# STLink_V3E_Module.net
KiCad netlist of a schematic drawn in Altium Designer
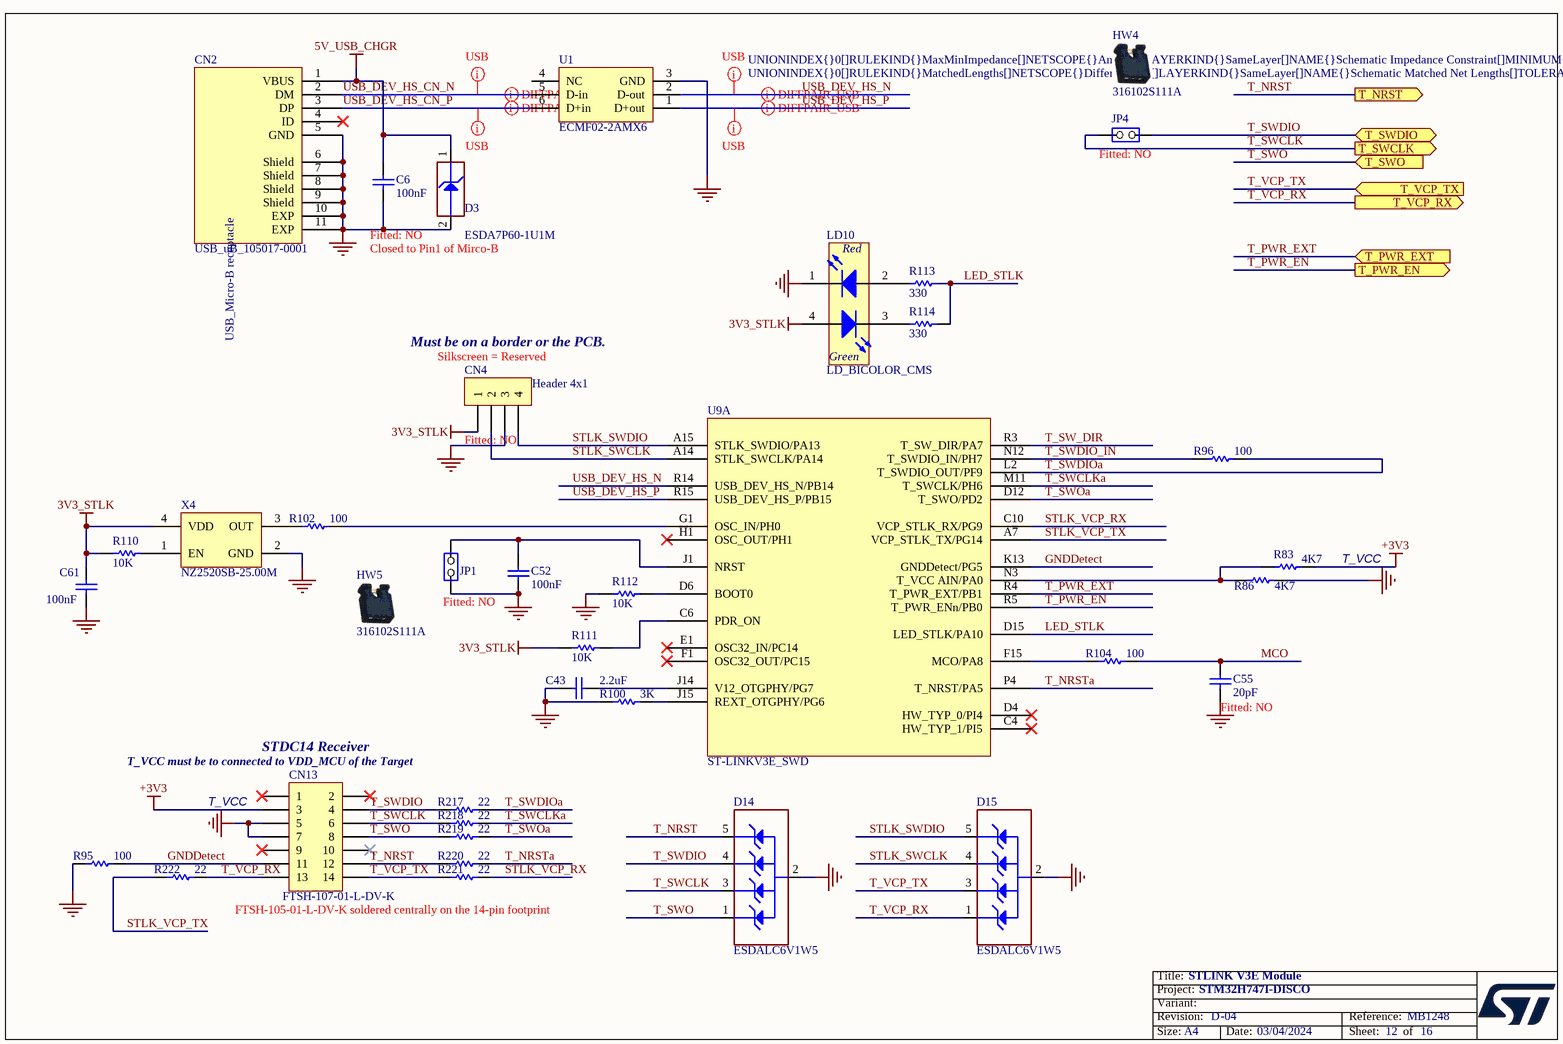
[diagram p0: STLink_V3E_Module.SchDoc]

(export (version "E")
  (design (tool "Eeschema 10.0.6"))
  (components
    (comp (ref "C6")
      (value "100nF")
      (footprint "0402C")
      (description "Capacitor,20pF,50V,NPO,5%,0402")
      (fields
        (field (name "INTERNAL_PART_NUMBER") "MCD-00016")
        (field (name "MANUFACTURER_PART_NUMBER") "CC0402JRNPO9BN200")
        (field (name "FITTED") "NO")
        (field (name "PROVIDED_BY") "Subcon")
      )
      (libsource (lib "MCD_PARTS_database") (part "Capacitor"))
    )
    (comp (ref "C43")
      (value "2.2uF")
      (footprint "0603C")
      (description "Capacitor,2.2uF,10V, X5R,10%,0603")
      (fields
        (field (name "INTERNAL_PART_NUMBER") "MCD-00012")
        (field (name "MANUFACTURER_PART_NUMBER") "CC0603KRX5R6BB225")
        (field (name "PROVIDED_BY") "Subcon")
      )
      (libsource (lib "MCD_PARTS_database") (part "Capacitor"))
    )
    (comp (ref "C52")
      (value "100nF")
      (footprint "0402C")
      (description "Capacitor,100nF,16V,X7R,10%,0402")
      (fields
        (field (name "INTERNAL_PART_NUMBER") "MCD-00102")
        (field (name "MANUFACTURER_PART_NUMBER") "CC0402KRX7R7BB104")
        (field (name "PROVIDED_BY") "Subcon")
      )
      (libsource (lib "MCD_PARTS_database") (part "Capacitor"))
    )
    (comp (ref "C55")
      (value "20pF")
      (footprint "0402C")
      (description "Capacitor,20pF,50V,NPO,5%,0402")
      (fields
        (field (name "INTERNAL_PART_NUMBER") "MCD-00016")
        (field (name "MANUFACTURER_PART_NUMBER") "CC0402JRNPO9BN200")
        (field (name "FITTED") "NO")
        (field (name "PROVIDED_BY") "Subcon")
      )
      (libsource (lib "MCD_PARTS_database") (part "Capacitor"))
    )
    (comp (ref "C61")
      (value "100nF")
      (footprint "0402C")
      (description "Capacitor,100nF,16V,X7R,10%,0402")
      (fields
        (field (name "INTERNAL_PART_NUMBER") "MCD-00102")
        (field (name "MANUFACTURER_PART_NUMBER") "CC0402KRX7R7BB104")
        (field (name "PROVIDED_BY") "Subcon")
      )
      (libsource (lib "MCD_PARTS_database") (part "Capacitor"))
    )
    (comp (ref "CN2")
      (value "USB_uB_105017-0001")
      (footprint "MICRO_USB_B_105017")
      (description "USB-MICRO-B, 0.65mm, RA, SMT, Bottom Mount,")
      (fields
        (field (name "INTERNAL_PART_NUMBER") "MCD-00028")
        (field (name "MANUFACTURER_PART_NUMBER") "1050170001")
        (field (name "PROVIDED_BY") "Subcon")
      )
      (libsource (lib "MCD_PARTS_database") (part "USB_uB_105017.0001"))
    )
    (comp (ref "CN4")
      (value "Header 4x1")
      (footprint "HDR_1X4_2R54")
      (description "Header, 4x1, 2,54mm, VR, TH, Height 5.84mm/2.54mm")
      (fields
        (field (name "INTERNAL_PART_NUMBER") "MCD-00029")
        (field (name "MANUFACTURER_PART_NUMBER") "TSW-104-07-G-S")
        (field (name "FITTED") "NO")
        (field (name "PROVIDED_BY") "Subcon")
      )
      (libsource (lib "MCD_PARTS_database") (part "Header 4x1"))
    )
    (comp (ref "CN13")
      (value "FTSH-107-01-L-DV-K")
      (footprint "FTSH-107-01-L-DV_B")
      (description "Header 7x2, 1.27mm, Dual row, Straight")
      (fields
        (field (name "INTERNAL_PART_NUMBER") "MCD-00592")
        (field (name "MANUFACTURER_PART_NUMBER") "FTSH-107-01-L-DV-009-ES-A")
        (field (name "PROVIDED_BY") "Subcon")
      )
      (libsource (lib "MCD_PARTS_database") (part "Header 7x2"))
    )
    (comp (ref "D3")
      (value "ESDA7P60-1U1M")
      (footprint "DO_2SM_1R6X1_21")
      (description "Dual Transil array for ESD protection")
      (libsource (lib "MCD_TEMP_PCH") (part "ESDALC6V1-1U2"))
    )
    (comp (ref "D14")
      (value "ESDALC6V1W5")
      (footprint "SC70-5")
      (description "Dual Transil array for ESD protection")
      (libsource (lib "MB1167_1") (part "ESDALC6V1W5"))
    )
    (comp (ref "D15")
      (value "ESDALC6V1W5")
      (footprint "SC70-5")
      (description "Dual Transil array for ESD protection")
      (libsource (lib "MB1167_1") (part "ESDALC6V1W5"))
    )
    (comp (ref "HW4")
      (value "316102S111A")
      (description "Jumper, 2.54mm, Black, 3A, 6mm, 20mR")
      (fields (field (name "INTERNAL_PART_NUMBER") "MCD-01849") (field (name "MANUFACTURER") "JIUBABA"))
      (libsource (lib "MCD_PARTS_database") (part "JUMPER_OPEN"))
    )
    (comp (ref "HW5")
      (value "316102S111A")
      (description "Jumper, 2.54mm, Black, 3A, 6mm, 20mR")
      (fields (field (name "INTERNAL_PART_NUMBER") "MCD-01849") (field (name "MANUFACTURER") "JIUBABA"))
      (libsource (lib "MCD_PARTS_database") (part "JUMPER_OPEN"))
    )
    (comp (ref "JP1")
      (value "Jumper Header 2x1")
      (footprint "SIP2")
      (description "Header, 2x1, 2,54mm, VR, TH, Height 5.84mm/2.54mm")
      (fields
        (field (name "INTERNAL_PART_NUMBER") "MCD-00045")
        (field (name "MANUFACTURER_PART_NUMBER") "TSW-102-07-G-S")
        (field (name "FITTED") "NO")
        (field (name "PROVIDED_BY") "Subcon")
      )
      (libsource (lib "MCD_PARTS_database") (part "Jumper Header 2x1"))
    )
    (comp (ref "JP4")
      (value "Jumper Header 2x1")
      (footprint "SIP2")
      (description "Header, 2x1, 2,54mm, VR, TH, Height 5.84mm/2.54mm")
      (fields
        (field (name "INTERNAL_PART_NUMBER") "MCD-00045")
        (field (name "MANUFACTURER_PART_NUMBER") "TSW-102-07-x-S")
        (field (name "FITTED") "NO")
        (field (name "PROVIDED_BY") "Subcon")
      )
      (libsource (lib "MCD_PARTS_database") (part "Jumper Header 2x1"))
    )
    (comp (ref "LD10")
      (value "LD_BICOLOR_CMS")
      (footprint "LED2_3528")
      (description "LED Bicolor")
      (fields
        (field (name "INTERNAL_PART_NUMBER") "MCD-00051")
        (field (name "MANUFACTURER_PART_NUMBER") "HSMF-A201-A00J1")
        (field (name "PROVIDED_BY") "Subcon")
      )
      (libsource (lib "MCD_PARTS_database") (part "LD_BICOLOR_CMS"))
    )
    (comp (ref "R83")
      (value "4K7")
      (footprint "0402R")
      (description "Resistor,4K7,0402,1%,1/16W")
      (fields
        (field (name "INTERNAL_PART_NUMBER") "MCD-00065")
        (field (name "MANUFACTURER_PART_NUMBER") "RC0402FR-074K7L")
        (field (name "PROVIDED_BY") "Subcon")
      )
      (libsource (lib "MCD_PARTS_database") (part "Resistor"))
    )
    (comp (ref "R86")
      (value "4K7")
      (footprint "0402R")
      (description "Resistor,4K7,0402,1%,1/16W")
      (fields
        (field (name "INTERNAL_PART_NUMBER") "MCD-00065")
        (field (name "MANUFACTURER_PART_NUMBER") "RC0402FR-074K7L")
        (field (name "PROVIDED_BY") "Subcon")
      )
      (libsource (lib "MCD_PARTS_database") (part "Resistor"))
    )
    (comp (ref "R95")
      (value "100")
      (footprint "0402R")
      (description "Resistor,100R,0402,1%,1/16W")
      (fields
        (field (name "INTERNAL_PART_NUMBER") "MCD-00119")
        (field (name "MANUFACTURER_PART_NUMBER") "RC0402FR-07100RL")
        (field (name "PROVIDED_BY") "Subcon")
      )
      (libsource (lib "MCD_PARTS_database") (part "Resistor"))
    )
    (comp (ref "R96")
      (value "100")
      (footprint "0402R")
      (description "Resistor,100R,0402,1%,1/16W")
      (fields
        (field (name "INTERNAL_PART_NUMBER") "MCD-00119")
        (field (name "MANUFACTURER_PART_NUMBER") "RC0402FR-07100RL")
        (field (name "PROVIDED_BY") "Subcon")
      )
      (libsource (lib "MCD_PARTS_database") (part "Resistor"))
    )
    (comp (ref "R100")
      (value "3K")
      (footprint "0402R")
      (description "Resistor,3K,0402,1%,1/16W")
      (fields
        (field (name "INTERNAL_PART_NUMBER") "MCD-00185")
        (field (name "MANUFACTURER_PART_NUMBER") "RC0402FR-073KL")
        (field (name "PROVIDED_BY") "Subcon")
      )
      (libsource (lib "MCD_PARTS_database") (part "Resistor"))
    )
    (comp (ref "R102")
      (value "100")
      (footprint "0402R")
      (description "Resistor,100R,0402,1%,1/16W")
      (fields
        (field (name "INTERNAL_PART_NUMBER") "MCD-00119")
        (field (name "MANUFACTURER_PART_NUMBER") "RC0402FR-07100RL")
        (field (name "PROVIDED_BY") "Subcon")
      )
      (libsource (lib "MCD_PARTS_database") (part "Resistor"))
    )
    (comp (ref "R104")
      (value "100")
      (footprint "0402R")
      (description "Resistor,100R,0402,1%,1/16W")
      (fields
        (field (name "INTERNAL_PART_NUMBER") "MCD-00119")
        (field (name "MANUFACTURER_PART_NUMBER") "RC0402FR-07100RL")
        (field (name "PROVIDED_BY") "Subcon")
      )
      (libsource (lib "MCD_PARTS_database") (part "Resistor"))
    )
    (comp (ref "R110")
      (value "10K")
      (footprint "0402R")
      (description "Resistor,10K,0402,1%,1/16W")
      (fields
        (field (name "INTERNAL_PART_NUMBER") "MCD-00053")
        (field (name "MANUFACTURER_PART_NUMBER") "RC0402FR-0710KL")
        (field (name "PROVIDED_BY") "subcon")
      )
      (libsource (lib "MCD_PARTS_database") (part "Resistor"))
    )
    (comp (ref "R111")
      (value "10K")
      (footprint "0402R")
      (description "Resistor,10K,0402,1%,1/16W")
      (fields
        (field (name "INTERNAL_PART_NUMBER") "MCD-00053")
        (field (name "MANUFACTURER_PART_NUMBER") "RC0402FR-0710KL")
        (field (name "PROVIDED_BY") "subcon")
      )
      (libsource (lib "MCD_PARTS_database") (part "Resistor"))
    )
    (comp (ref "R112")
      (value "10K")
      (footprint "0402R")
      (description "Resistor,10K,0402,1%,1/16W")
      (fields
        (field (name "INTERNAL_PART_NUMBER") "MCD-00053")
        (field (name "MANUFACTURER_PART_NUMBER") "RC0402FR-0710KL")
        (field (name "PROVIDED_BY") "subcon")
      )
      (libsource (lib "MCD_PARTS_database") (part "Resistor"))
    )
    (comp (ref "R113")
      (value "330")
      (footprint "0603R")
      (description "Resistor,330R,0603,1%,1/10W")
      (fields
        (field (name "INTERNAL_PART_NUMBER") "MCD-00197")
        (field (name "MANUFACTURER_PART_NUMBER") "RC0603FR-07330RL")
        (field (name "PROVIDED_BY") "Subcon")
      )
      (libsource (lib "MCD_PARTS_database") (part "Resistor"))
    )
    (comp (ref "R114")
      (value "330")
      (footprint "0603R")
      (description "Resistor,330R,0603,1%,1/10W")
      (fields
        (field (name "INTERNAL_PART_NUMBER") "MCD-00197")
        (field (name "MANUFACTURER_PART_NUMBER") "RC0603FR-07330RL")
        (field (name "PROVIDED_BY") "Subcon")
      )
      (libsource (lib "MCD_PARTS_database") (part "Resistor"))
    )
    (comp (ref "R217")
      (value "22")
      (footprint "0603R")
      (description "Resistor")
      (fields (field (name "PUBLISHER") "Altium Limited"))
      (libsource (lib "Miscellaneous Devices") (part "Res1"))
    )
    (comp (ref "R218")
      (value "22")
      (footprint "0603R")
      (description "Resistor")
      (fields (field (name "PUBLISHER") "Altium Limited"))
      (libsource (lib "Miscellaneous Devices") (part "Res1"))
    )
    (comp (ref "R219")
      (value "22")
      (footprint "0603R")
      (description "Resistor")
      (fields (field (name "PUBLISHER") "Altium Limited"))
      (libsource (lib "Miscellaneous Devices") (part "Res1"))
    )
    (comp (ref "R220")
      (value "22")
      (footprint "0603R")
      (description "Resistor")
      (fields (field (name "PUBLISHER") "Altium Limited"))
      (libsource (lib "Miscellaneous Devices") (part "Res1"))
    )
    (comp (ref "R221")
      (value "22")
      (footprint "0603R")
      (description "Resistor")
      (fields (field (name "PUBLISHER") "Altium Limited"))
      (libsource (lib "Miscellaneous Devices") (part "Res1"))
    )
    (comp (ref "R222")
      (value "22")
      (footprint "0603R")
      (description "Resistor")
      (fields (field (name "PUBLISHER") "Altium Limited"))
      (libsource (lib "Miscellaneous Devices") (part "Res1"))
    )
    (comp (ref "U1")
      (value "ECMF02-2AMX6")
      (footprint "DFN6_0R5_1R7X1R5")
      (description "Common mode filter with ESD protection for USB 2.0 interface")
      (libsource (lib "MB1248_1") (part "ECMF02-2AMX6"))
    )
    (comp (ref "U9")
      (value "ST-LINKV3E_SWD")
      (footprint "BGA176_0R65_10x10")
      (description "STM32F723IEK  (STM32F7 LittleBirdie) BGA176")
      (fields (field (name "INTERNAL_PART_NUMBER") "MCD-00596"))
      (libsource (lib "MB1248_1") (part "ST-LINKV3E_SWD"))
    )
    (comp (ref "X4")
      (value "NZ2520SB-25.00M")
      (footprint "OSC_4SM_2R5X2")
      (description "Oscillator 25.00Mhz, -+50PPM, 3.3V, Temp -55 to +125癈")
      (libsource (lib "MCD_TOOLS") (part "OSC_25M_NZ2520SB"))
    )
  )
  (nets
    (net (code "1") (name "+3V3") (class "Default")
      (node (ref "CN13") (pin "3") (pinfunction "3_3") (pintype "passive"))
      (node (ref "R83") (pin "2") (pinfunction "2_2") (pintype "passive"))
    )
    (net (code "2") (name "/GNDDetect") (class "Default")
      (node (ref "CN13") (pin "11") (pinfunction "11_11") (pintype "passive"))
      (node (ref "R95") (pin "2") (pinfunction "2_2") (pintype "passive"))
      (node (ref "U9") (pin "K13") (pinfunction "GNDDetect/PG5_K13") (pintype "passive"))
    )
    (net (code "3") (name "/LED_STLK") (class "Default")
      (node (ref "R113") (pin "2") (pinfunction "2_2") (pintype "passive"))
      (node (ref "R114") (pin "2") (pinfunction "2_2") (pintype "passive"))
      (node (ref "U9") (pin "D15") (pinfunction "LED_STLK/PA10_D15") (pintype "passive"))
    )
    (net (code "4") (name "/MCO") (class "Default")
      (node (ref "C55") (pin "2") (pinfunction "2_2") (pintype "passive"))
      (node (ref "R104") (pin "2") (pinfunction "2_2") (pintype "passive"))
    )
    (net (code "5") (name "/STLK_SWCLK") (class "Default")
      (node (ref "CN4") (pin "2") (pinfunction "2_2") (pintype "passive"))
      (node (ref "D15") (pin "4") (pinfunction "IO3_4") (pintype "passive"))
      (node (ref "U9") (pin "A14") (pinfunction "STLK_SWCLK/PA14_A14") (pintype "passive"))
    )
    (net (code "6") (name "/STLK_SWDIO") (class "Default")
      (node (ref "CN4") (pin "4") (pinfunction "4_4") (pintype "passive"))
      (node (ref "D15") (pin "5") (pinfunction "IO4_5") (pintype "passive"))
      (node (ref "U9") (pin "A15") (pinfunction "STLK_SWDIO/PA13_A15") (pintype "passive"))
    )
    (net (code "7") (name "/STLK_VCP_RX") (class "Default")
      (node (ref "R221") (pin "1") (pinfunction "1_1") (pintype "passive"))
      (node (ref "U9") (pin "C10") (pinfunction "VCP_STLK_RX/PG9_C10") (pintype "passive"))
    )
    (net (code "8") (name "/STLK_VCP_TX") (class "Default")
      (node (ref "R222") (pin "2") (pinfunction "2_2") (pintype "passive"))
      (node (ref "U9") (pin "A7") (pinfunction "VCP_STLK_TX/PG14_A7") (pintype "passive"))
    )
    (net (code "9") (name "/T_NRST") (class "Default")
      (node (ref "CN13") (pin "12") (pinfunction "12_12") (pintype "passive"))
      (node (ref "D14") (pin "5") (pinfunction "IO4_5") (pintype "passive"))
      (node (ref "R220") (pin "2") (pinfunction "2_2") (pintype "passive"))
    )
    (net (code "10") (name "/T_NRSTa") (class "Default")
      (node (ref "R220") (pin "1") (pinfunction "1_1") (pintype "passive"))
      (node (ref "U9") (pin "P4") (pinfunction "T_NRST/PA5_P4") (pintype "passive"))
    )
    (net (code "11") (name "/T_PWR_EN") (class "Default")
      (node (ref "U9") (pin "R5") (pinfunction "T_PWR_ENn/PB0_R5") (pintype "passive"))
    )
    (net (code "12") (name "/T_PWR_EXT") (class "Default")
      (node (ref "U9") (pin "R4") (pinfunction "T_PWR_EXT/PB1_R4") (pintype "passive"))
    )
    (net (code "13") (name "/T_SWCLK") (class "Default")
      (node (ref "CN13") (pin "6") (pinfunction "6_6") (pintype "passive"))
      (node (ref "D14") (pin "3") (pinfunction "IO2_3") (pintype "passive"))
      (node (ref "JP4") (pin "1") (pinfunction "COMMON_1") (pintype "passive"))
      (node (ref "R218") (pin "2") (pinfunction "2_2") (pintype "passive"))
    )
    (net (code "14") (name "/T_SWCLKa") (class "Default")
      (node (ref "R218") (pin "1") (pinfunction "1_1") (pintype "passive"))
      (node (ref "U9") (pin "M11") (pinfunction "T_SWCLK/PH6_M11") (pintype "passive"))
    )
    (net (code "15") (name "/T_SWDIO") (class "Default")
      (node (ref "CN13") (pin "4") (pinfunction "4_4") (pintype "passive"))
      (node (ref "D14") (pin "4") (pinfunction "IO3_4") (pintype "passive"))
      (node (ref "JP4") (pin "2") (pinfunction "NO_2") (pintype "passive"))
      (node (ref "R217") (pin "2") (pinfunction "2_2") (pintype "passive"))
    )
    (net (code "16") (name "/T_SWDIO_IN") (class "Default")
      (node (ref "R96") (pin "1") (pinfunction "1_1") (pintype "passive"))
      (node (ref "U9") (pin "N12") (pinfunction "T_SWDIO_IN/PH7_N12") (pintype "passive"))
    )
    (net (code "17") (name "/T_SWDIOa") (class "Default")
      (node (ref "R217") (pin "1") (pinfunction "1_1") (pintype "passive"))
      (node (ref "R96") (pin "2") (pinfunction "2_2") (pintype "passive"))
      (node (ref "U9") (pin "L2") (pinfunction "T_SWDIO_OUT/PF9_L2") (pintype "passive"))
    )
    (net (code "18") (name "/T_SWO") (class "Default")
      (node (ref "CN13") (pin "8") (pinfunction "8_8") (pintype "passive"))
      (node (ref "D14") (pin "1") (pinfunction "IO1_1") (pintype "passive"))
      (node (ref "R219") (pin "2") (pinfunction "2_2") (pintype "passive"))
    )
    (net (code "19") (name "/T_SWOa") (class "Default")
      (node (ref "R219") (pin "1") (pinfunction "1_1") (pintype "passive"))
      (node (ref "U9") (pin "D12") (pinfunction "T_SWO/PD2_D12") (pintype "passive"))
    )
    (net (code "20") (name "/T_SW_DIR") (class "Default")
      (node (ref "U9") (pin "R3") (pinfunction "T_SW_DIR/PA7_R3") (pintype "passive"))
    )
    (net (code "21") (name "/T_VCP_RX") (class "Default")
      (node (ref "CN13") (pin "13") (pinfunction "13_13") (pintype "passive"))
      (node (ref "D15") (pin "1") (pinfunction "IO1_1") (pintype "passive"))
      (node (ref "R222") (pin "1") (pinfunction "1_1") (pintype "passive"))
    )
    (net (code "22") (name "/T_VCP_TX") (class "Default")
      (node (ref "CN13") (pin "14") (pinfunction "14_14") (pintype "passive"))
      (node (ref "D15") (pin "3") (pinfunction "IO2_3") (pintype "passive"))
      (node (ref "R221") (pin "2") (pinfunction "2_2") (pintype "passive"))
    )
    (net (code "23") (name "/USB_DEV_HS_CN_N") (class "Default")
      (node (ref "CN2") (pin "2") (pinfunction "DM_2") (pintype "passive"))
      (node (ref "U1") (pin "5") (pinfunction "D-in_5") (pintype "passive"))
    )
    (net (code "24") (name "/USB_DEV_HS_CN_P") (class "Default")
      (node (ref "CN2") (pin "3") (pinfunction "DP_3") (pintype "passive"))
      (node (ref "U1") (pin "6") (pinfunction "D+in_6") (pintype "passive"))
    )
    (net (code "25") (name "/USB_DEV_HS_N") (class "Default")
      (node (ref "U1") (pin "2") (pinfunction "D-out_2") (pintype "passive"))
      (node (ref "U9") (pin "R14") (pinfunction "USB_DEV_HS_N/PB14_R14") (pintype "passive"))
    )
    (net (code "26") (name "/USB_DEV_HS_P") (class "Default")
      (node (ref "U1") (pin "1") (pinfunction "D+out_1") (pintype "passive"))
      (node (ref "U9") (pin "R15") (pinfunction "USB_DEV_HS_P/PB15_R15") (pintype "passive"))
    )
    (net (code "27") (name "3V3_STLK") (class "Default")
      (node (ref "C61") (pin "2") (pinfunction "2_2") (pintype "passive"))
      (node (ref "CN4") (pin "1") (pinfunction "1_1") (pintype "passive"))
      (node (ref "LD10") (pin "4") (pinfunction "YellowGreen_anode_4") (pintype "passive"))
      (node (ref "R110") (pin "1") (pinfunction "1_1") (pintype "passive"))
      (node (ref "R111") (pin "1") (pinfunction "1_1") (pintype "passive"))
      (node (ref "X4") (pin "4") (pinfunction "VDD_4") (pintype "passive"))
    )
    (net (code "28") (name "5V_USB_CHGR") (class "Default")
      (node (ref "C6") (pin "2") (pinfunction "2_2") (pintype "passive"))
      (node (ref "CN2") (pin "1") (pinfunction "VBUS_1") (pintype "passive"))
      (node (ref "D3") (pin "1") (pinfunction "IO1_1") (pintype "passive"))
    )
    (net (code "29") (name "GND") (class "Default")
      (node (ref "C43") (pin "1") (pinfunction "1_1") (pintype "passive"))
      (node (ref "C52") (pin "1") (pinfunction "1_1") (pintype "passive"))
      (node (ref "C55") (pin "1") (pinfunction "1_1") (pintype "passive"))
      (node (ref "C6") (pin "1") (pinfunction "1_1") (pintype "passive"))
      (node (ref "C61") (pin "1") (pinfunction "1_1") (pintype "passive"))
      (node (ref "CN13") (pin "5") (pinfunction "5_5") (pintype "passive"))
      (node (ref "CN13") (pin "7") (pinfunction "7_7") (pintype "passive"))
      (node (ref "CN2") (pin "10") (pinfunction "EXP_10") (pintype "passive"))
      (node (ref "CN2") (pin "11") (pinfunction "EXP_11") (pintype "passive"))
      (node (ref "CN2") (pin "5") (pinfunction "GND_5") (pintype "passive"))
      (node (ref "CN2") (pin "6") (pinfunction "Shield_6") (pintype "passive"))
      (node (ref "CN2") (pin "7") (pinfunction "Shield_7") (pintype "passive"))
      (node (ref "CN2") (pin "8") (pinfunction "Shield_8") (pintype "passive"))
      (node (ref "CN2") (pin "9") (pinfunction "Shield_9") (pintype "passive"))
      (node (ref "CN4") (pin "3") (pinfunction "3_3") (pintype "passive"))
      (node (ref "D14") (pin "2") (pinfunction "GND_2") (pintype "passive"))
      (node (ref "D15") (pin "2") (pinfunction "GND_2") (pintype "passive"))
      (node (ref "D3") (pin "2") (pinfunction "GND_2") (pintype "passive"))
      (node (ref "JP1") (pin "1") (pinfunction "COMMON_1") (pintype "passive"))
      (node (ref "LD10") (pin "1") (pinfunction "RED_cathode_1") (pintype "passive"))
      (node (ref "R100") (pin "1") (pinfunction "1_1") (pintype "passive"))
      (node (ref "R112") (pin "1") (pinfunction "1_1") (pintype "passive"))
      (node (ref "R86") (pin "2") (pinfunction "2_2") (pintype "passive"))
      (node (ref "R95") (pin "1") (pinfunction "1_1") (pintype "passive"))
      (node (ref "U1") (pin "3") (pinfunction "GND_3") (pintype "passive"))
      (node (ref "X4") (pin "2") (pinfunction "GND_2") (pintype "passive"))
    )
    (net (code "30") (name "Net-(JP1-NO)") (class "Default")
      (node (ref "C52") (pin "2") (pinfunction "2_2") (pintype "passive"))
      (node (ref "JP1") (pin "2") (pinfunction "NO_2") (pintype "passive"))
      (node (ref "U9") (pin "J1") (pinfunction "NRST_J1") (pintype "passive"))
    )
    (net (code "31") (name "Net-(LD10-Red_anode)") (class "Default")
      (node (ref "LD10") (pin "2") (pinfunction "Red_anode_2") (pintype "passive"))
      (node (ref "R113") (pin "1") (pinfunction "1_1") (pintype "passive"))
    )
    (net (code "32") (name "Net-(LD10-YellowGreen_cathode)") (class "Default")
      (node (ref "LD10") (pin "3") (pinfunction "YellowGreen_cathode_3") (pintype "passive"))
      (node (ref "R114") (pin "1") (pinfunction "1_1") (pintype "passive"))
    )
    (net (code "33") (name "Net-(U9A-BOOT0)") (class "Default")
      (node (ref "R112") (pin "2") (pinfunction "2_2") (pintype "passive"))
      (node (ref "U9") (pin "D6") (pinfunction "BOOT0_D6") (pintype "passive"))
    )
    (net (code "34") (name "Net-(U9A-MCO{slash}PA8)") (class "Default")
      (node (ref "R104") (pin "1") (pinfunction "1_1") (pintype "passive"))
      (node (ref "U9") (pin "F15") (pinfunction "MCO/PA8_F15") (pintype "passive"))
    )
    (net (code "35") (name "Net-(U9A-OSC_IN{slash}PH0)") (class "Default")
      (node (ref "R102") (pin "2") (pinfunction "2_2") (pintype "passive"))
      (node (ref "U9") (pin "G1") (pinfunction "OSC_IN/PH0_G1") (pintype "passive"))
    )
    (net (code "36") (name "Net-(U9A-PDR_ON)") (class "Default")
      (node (ref "R111") (pin "2") (pinfunction "2_2") (pintype "passive"))
      (node (ref "U9") (pin "C6") (pinfunction "PDR_ON_C6") (pintype "passive"))
    )
    (net (code "37") (name "Net-(U9A-REXT_OTGPHY{slash}PG6)") (class "Default")
      (node (ref "R100") (pin "2") (pinfunction "2_2") (pintype "passive"))
      (node (ref "U9") (pin "J15") (pinfunction "REXT_OTGPHY/PG6_J15") (pintype "passive"))
    )
    (net (code "38") (name "Net-(U9A-T_VCC_AIN{slash}PA0)") (class "Default")
      (node (ref "R83") (pin "1") (pinfunction "1_1") (pintype "passive"))
      (node (ref "R86") (pin "1") (pinfunction "1_1") (pintype "passive"))
      (node (ref "U9") (pin "N3") (pinfunction "T_VCC_AIN/PA0_N3") (pintype "passive"))
    )
    (net (code "39") (name "Net-(U9A-V12_OTGPHY{slash}PG7)") (class "Default")
      (node (ref "C43") (pin "2") (pinfunction "2_2") (pintype "passive"))
      (node (ref "U9") (pin "J14") (pinfunction "V12_OTGPHY/PG7_J14") (pintype "passive"))
    )
    (net (code "40") (name "Net-(X4-EN)") (class "Default")
      (node (ref "R110") (pin "2") (pinfunction "2_2") (pintype "passive"))
      (node (ref "X4") (pin "1") (pinfunction "EN_1") (pintype "passive"))
    )
    (net (code "41") (name "Net-(X4-OUT)") (class "Default")
      (node (ref "R102") (pin "1") (pinfunction "1_1") (pintype "passive"))
      (node (ref "X4") (pin "3") (pinfunction "OUT_3") (pintype "passive"))
    )
    (net (code "42") (name "unconnected-(CN2-ID-Pad4)") (class "Default")
      (node (ref "CN2") (pin "4") (pinfunction "ID_4") (pintype "passive+no_connect"))
    )
    (net (code "43") (name "unconnected-(CN13-Pad1)") (class "Default")
      (node (ref "CN13") (pin "1") (pinfunction "1_1") (pintype "passive+no_connect"))
    )
    (net (code "44") (name "unconnected-(CN13-Pad2)") (class "Default")
      (node (ref "CN13") (pin "2") (pinfunction "2_2") (pintype "passive+no_connect"))
    )
    (net (code "45") (name "unconnected-(CN13-Pad9)") (class "Default")
      (node (ref "CN13") (pin "9") (pinfunction "9_9") (pintype "passive+no_connect"))
    )
    (net (code "46") (name "unconnected-(CN13-Pad10)") (class "Default")
      (node (ref "CN13") (pin "10") (pinfunction "10_10") (pintype "passive+no_connect"))
    )
    (net (code "47") (name "unconnected-(U1-NC-Pad4)") (class "Default")
      (node (ref "U1") (pin "4") (pinfunction "NC_4") (pintype "passive"))
    )
    (net (code "48") (name "unconnected-(U9A-HW_TYP_0{slash}PI4-PadD4)") (class "Default")
      (node (ref "U9") (pin "D4") (pinfunction "HW_TYP_0/PI4_D4") (pintype "passive+no_connect"))
    )
    (net (code "49") (name "unconnected-(U9A-HW_TYP_1{slash}PI5-PadC4)") (class "Default")
      (node (ref "U9") (pin "C4") (pinfunction "HW_TYP_1/PI5_C4") (pintype "passive+no_connect"))
    )
    (net (code "50") (name "unconnected-(U9A-OSC32_IN{slash}PC14-PadE1)") (class "Default")
      (node (ref "U9") (pin "E1") (pinfunction "OSC32_IN/PC14_E1") (pintype "passive+no_connect"))
    )
    (net (code "51") (name "unconnected-(U9A-OSC32_OUT{slash}PC15-PadF1)") (class "Default")
      (node (ref "U9") (pin "F1") (pinfunction "OSC32_OUT/PC15_F1") (pintype "passive+no_connect"))
    )
    (net (code "52") (name "unconnected-(U9A-OSC_OUT{slash}PH1-PadH1)") (class "Default")
      (node (ref "U9") (pin "H1") (pinfunction "OSC_OUT/PH1_H1") (pintype "passive+no_connect"))
    )
  )
)
